# SCH.net
KiCad netlist of a schematic drawn in Altium Designer
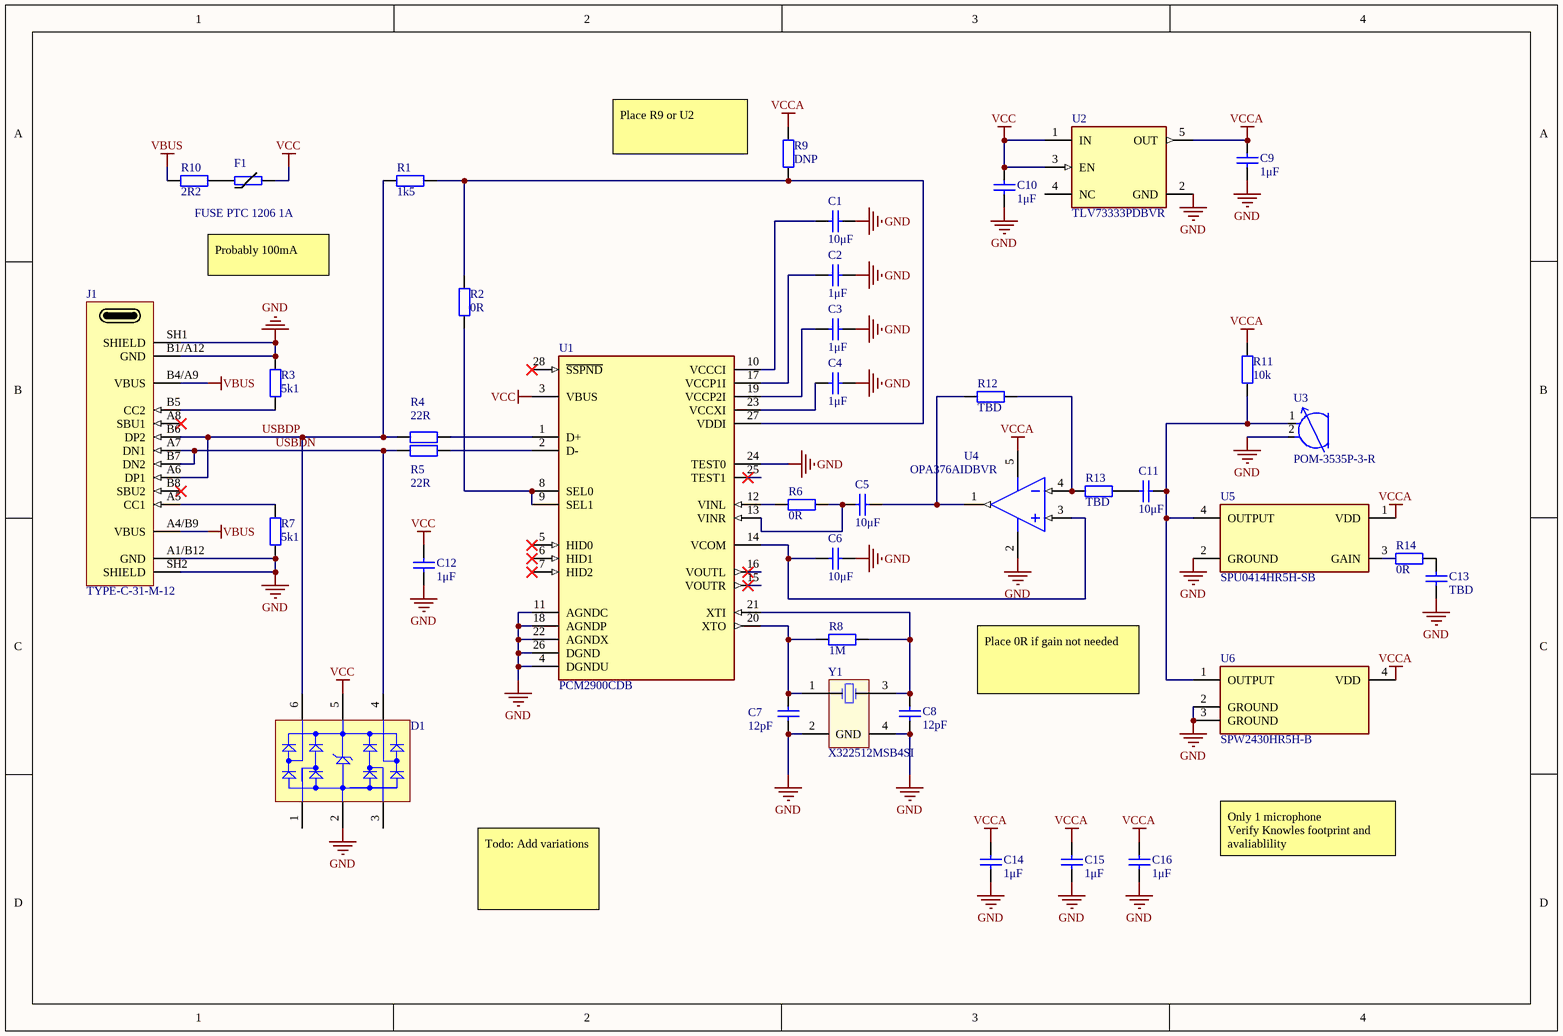
[diagram p0: SCH.SchDoc]

(export (version "E")
  (design (tool "Eeschema 10.0.6"))
  (components
    (comp (ref "C1")
      (value "10μF")
      (footprint "CAPC1206N")
      (description "Multilayer Ceramic Capacitors MLCC - SMD/SMT 10uF 50V 1206 RoHS")
      (fields
        (field (name "MFR") "CL31A106KBHNNNE")
        (field (name "MANUFACTURER") "Samsung Electro-Mechanics")
      )
      (libsource (lib "CAP") (part "Cap"))
    )
    (comp (ref "C2")
      (value "1μF")
      (footprint "CAPC0402N")
      (description "Multilayer Ceramic Capacitors MLCC - SMD/SMT 1uF 25V 0402 RoHS")
      (fields
        (field (name "MFR") "CL05A105KA5NQNC")
        (field (name "MANUFACTURER") "Samsung Electro-Mechanics")
      )
      (libsource (lib "CAP") (part "Cap"))
    )
    (comp (ref "C3")
      (value "1μF")
      (footprint "CAPC0402N")
      (description "Multilayer Ceramic Capacitors MLCC - SMD/SMT 1uF 25V 0402 RoHS")
      (fields
        (field (name "MFR") "CL05A105KA5NQNC")
        (field (name "MANUFACTURER") "Samsung Electro-Mechanics")
      )
      (libsource (lib "CAP") (part "Cap"))
    )
    (comp (ref "C4")
      (value "1μF")
      (footprint "CAPC0402N")
      (description "Multilayer Ceramic Capacitors MLCC - SMD/SMT 1uF 25V 0402 RoHS")
      (fields
        (field (name "MFR") "CL05A105KA5NQNC")
        (field (name "MANUFACTURER") "Samsung Electro-Mechanics")
      )
      (libsource (lib "CAP") (part "Cap"))
    )
    (comp (ref "C5")
      (value "10μF")
      (footprint "CAPC1206N")
      (description "Multilayer Ceramic Capacitors MLCC - SMD/SMT 10uF 50V 1206 RoHS")
      (fields
        (field (name "MFR") "CL31A106KBHNNNE")
        (field (name "MANUFACTURER") "Samsung Electro-Mechanics")
      )
      (libsource (lib "CAP") (part "Cap"))
    )
    (comp (ref "C6")
      (value "10μF")
      (footprint "CAPC1206N")
      (description "Multilayer Ceramic Capacitors MLCC - SMD/SMT 10uF 50V 1206 RoHS")
      (fields
        (field (name "MFR") "CL31A106KBHNNNE")
        (field (name "MANUFACTURER") "Samsung Electro-Mechanics")
      )
      (libsource (lib "CAP") (part "Cap"))
    )
    (comp (ref "C7")
      (value "12pF")
      (footprint "CAPC0402N")
      (description "Multilayer Ceramic Capacitors MLCC - SMD/SMT 12pF 50V 0402 RoHS")
      (fields
        (field (name "MFR") "0402CG120J500NT")
        (field (name "MANUFACTURER") "Guangdong Fenghua Advanced Tech")
      )
      (libsource (lib "CAP") (part "Cap"))
    )
    (comp (ref "C8")
      (value "12pF")
      (footprint "CAPC0402N")
      (description "Multilayer Ceramic Capacitors MLCC - SMD/SMT 12pF 50V 0402 RoHS")
      (fields
        (field (name "MFR") "0402CG120J500NT")
        (field (name "MANUFACTURER") "Guangdong Fenghua Advanced Tech")
      )
      (libsource (lib "CAP") (part "Cap"))
    )
    (comp (ref "C9")
      (value "1μF")
      (footprint "CAPC0402N")
      (description "Multilayer Ceramic Capacitors MLCC - SMD/SMT 1uF 25V 0402 RoHS")
      (fields
        (field (name "MFR") "CL05A105KA5NQNC")
        (field (name "MANUFACTURER") "Samsung Electro-Mechanics")
      )
      (libsource (lib "CAP") (part "Cap"))
    )
    (comp (ref "C10")
      (value "1μF")
      (footprint "CAPC0402N")
      (description "Multilayer Ceramic Capacitors MLCC - SMD/SMT 1uF 25V 0402 RoHS")
      (fields
        (field (name "MFR") "CL05A105KA5NQNC")
        (field (name "MANUFACTURER") "Samsung Electro-Mechanics")
      )
      (libsource (lib "CAP") (part "Cap"))
    )
    (comp (ref "C11")
      (value "10μF")
      (footprint "CAPC1206N")
      (description "Multilayer Ceramic Capacitors MLCC - SMD/SMT 10uF 50V 1206 RoHS")
      (fields
        (field (name "MFR") "CL31A106KBHNNNE")
        (field (name "MANUFACTURER") "Samsung Electro-Mechanics")
      )
      (libsource (lib "CAP") (part "Cap"))
    )
    (comp (ref "C12")
      (value "1μF")
      (footprint "CAPC0402N")
      (description "Multilayer Ceramic Capacitors MLCC - SMD/SMT 1uF 25V 0402 RoHS")
      (fields
        (field (name "MFR") "CL05A105KA5NQNC")
        (field (name "MANUFACTURER") "Samsung Electro-Mechanics")
      )
      (libsource (lib "CAP") (part "Cap"))
    )
    (comp (ref "C13")
      (value "TBD")
      (footprint "CAPC0402N")
      (description "Multilayer Ceramic Capacitors MLCC - SMD/SMT 12pF 50V 0402 RoHS")
      (fields
        (field (name "MFR") "0402CG120J500NT")
        (field (name "MANUFACTURER") "Guangdong Fenghua Advanced Tech")
      )
      (libsource (lib "CAP") (part "Cap"))
    )
    (comp (ref "C14")
      (value "1μF")
      (footprint "CAPC0402N")
      (description "Multilayer Ceramic Capacitors MLCC - SMD/SMT 1uF 25V 0402 RoHS")
      (fields
        (field (name "MFR") "CL05A105KA5NQNC")
        (field (name "MANUFACTURER") "Samsung Electro-Mechanics")
      )
      (libsource (lib "CAP") (part "Cap"))
    )
    (comp (ref "C15")
      (value "1μF")
      (footprint "CAPC0402N")
      (description "Multilayer Ceramic Capacitors MLCC - SMD/SMT 1uF 25V 0402 RoHS")
      (fields
        (field (name "MFR") "CL05A105KA5NQNC")
        (field (name "MANUFACTURER") "Samsung Electro-Mechanics")
      )
      (libsource (lib "CAP") (part "Cap"))
    )
    (comp (ref "C16")
      (value "1μF")
      (footprint "CAPC0402N")
      (description "Multilayer Ceramic Capacitors MLCC - SMD/SMT 1uF 25V 0402 RoHS")
      (fields
        (field (name "MFR") "CL05A105KA5NQNC")
        (field (name "MANUFACTURER") "Samsung Electro-Mechanics")
      )
      (libsource (lib "CAP") (part "Cap"))
    )
    (comp (ref "D1")
      (value "~")
      (footprint "SMTC-SOT23-6_V")
      (fields (field (name "MANUFACTURER") "PROTEK DEVICES") (field (name "MFR") "SRV05-4-P-T7"))
      (libsource (lib "JLC_basic") (part "STM-USB_DVI_HDMIULC6-4SC6X-SOT23-6L"))
    )
    (comp (ref "F1")
      (value "FUSE PTC 1206 1A")
      (footprint "FUSE1206N")
      (fields
        (field (name "VOLTAGE") "6V")
        (field (name "MANUFACTURER") "BOURNS")
        (field (name "MFR") "MF-NSMF050-2")
      )
      (libsource (lib "Fuse") (part "PTC-SMALL"))
    )
    (comp (ref "J1")
      (value "TYPE-C-31-M-12")
      (footprint "TYPE-C-31-M-12")
      (description "USB TYPE-C 2.0 16 PIN SMD")
      (fields (field (name "MANUFACTURER") "Korean Hroparts Elec"))
      (libsource (lib "TYPE-C-31-M-12") (part "TYPE-C-31-M-12"))
    )
    (comp (ref "R1")
      (value "1k5")
      (footprint "RESC0402N")
      (description "Chip Resistor - Surface Mount 1.5KOhms ±1% 1/16W 0402 RoHS")
      (fields (field (name "MFR") "0402WGF1501TCE") (field (name "MANUFACTURER") "Uniroyal Elec"))
      (libsource (lib "RES") (part "Res"))
    )
    (comp (ref "R2")
      (value "0R")
      (footprint "RESC0402N")
      (description "Chip Resistor - Surface Mount 0Ohms ±1% 1/16W 0402 RoHS")
      (fields (field (name "MFR") "0402WGF0000TCE") (field (name "MANUFACTURER") "Uniroyal Elec"))
      (libsource (lib "") (part "Res_1"))
    )
    (comp (ref "R3")
      (value "5k1")
      (footprint "RESC0402N")
      (description "Chip Resistor - Surface Mount 5.1KOhms ±1% 1/16W 0402 RoHS")
      (fields (field (name "MFR") "0402WGF5101TCE") (field (name "MANUFACTURER") "Uniroyal Elec"))
      (libsource (lib "") (part "Res_1"))
    )
    (comp (ref "R4")
      (value "22R")
      (footprint "RESC0402N")
      (description "Chip Resistor - Surface Mount 22Ohms ±1% 1/16W 0402 RoHS")
      (fields (field (name "MFR") "0402WGF220JTCE") (field (name "MANUFACTURER") "Uniroyal Elec"))
      (libsource (lib "RES") (part "Res"))
    )
    (comp (ref "R5")
      (value "22R")
      (footprint "RESC0402N")
      (description "Chip Resistor - Surface Mount 22Ohms ±1% 1/16W 0402 RoHS")
      (fields (field (name "MFR") "0402WGF220JTCE") (field (name "MANUFACTURER") "Uniroyal Elec"))
      (libsource (lib "RES") (part "Res"))
    )
    (comp (ref "R6")
      (value "0R")
      (footprint "RESC0402N")
      (description "Chip Resistor - Surface Mount 0Ohms ±1% 1/16W 0402 RoHS")
      (fields (field (name "MFR") "0402WGF0000TCE") (field (name "MANUFACTURER") "Uniroyal Elec"))
      (libsource (lib "RES") (part "Res"))
    )
    (comp (ref "R7")
      (value "5k1")
      (footprint "RESC0402N")
      (description "Chip Resistor - Surface Mount 5.1KOhms ±1% 1/16W 0402 RoHS")
      (fields (field (name "MFR") "0402WGF5101TCE") (field (name "MANUFACTURER") "Uniroyal Elec"))
      (libsource (lib "") (part "Res_1"))
    )
    (comp (ref "R8")
      (value "1M")
      (footprint "RESC0402N")
      (description "Chip Resistor - Surface Mount 1MOhms ±1% 1/16W 0402 RoHS")
      (fields (field (name "MFR") "0402WGF1004TCE") (field (name "MANUFACTURER") "Uniroyal Elec"))
      (libsource (lib "RES") (part "Res"))
    )
    (comp (ref "R9")
      (value "DNP")
      (footprint "RESC0402N")
      (description "Chip Resistor - Surface Mount 0Ohms ±1% 1/16W 0402 RoHS")
      (fields (field (name "MFR") "0402WGF0000TCE") (field (name "MANUFACTURER") "Uniroyal Elec"))
      (libsource (lib "") (part "Res_1"))
    )
    (comp (ref "R10")
      (value "2R2")
      (footprint "RESC0805N")
      (description "Chip Resistor - Surface Mount 2.2Ohms ±1% 1/8W 0805 RoHS")
      (fields (field (name "MFR") "0805W8F220KT5E") (field (name "MANUFACTURER") "Uniroyal Elec"))
      (libsource (lib "RES") (part "Res"))
    )
    (comp (ref "R11")
      (value "10k")
      (footprint "RESC0402N")
      (description "Chip Resistor - Surface Mount 10KOhms ±1% 1/16W 0402 RoHS")
      (fields (field (name "MFR") "0402WGF1002TCE") (field (name "MANUFACTURER") "Uniroyal Elec"))
      (libsource (lib "") (part "Res_1"))
    )
    (comp (ref "R12")
      (value "TBD")
      (footprint "RESC0402N")
      (description "Chip Resistor - Surface Mount 0Ohms ±1% 1/16W 0402 RoHS")
      (fields (field (name "MFR") "0402WGF0000TCE") (field (name "MANUFACTURER") "Uniroyal Elec"))
      (libsource (lib "RES") (part "Res"))
    )
    (comp (ref "R13")
      (value "TBD")
      (footprint "RESC0402N")
      (description "Chip Resistor - Surface Mount 0Ohms ±1% 1/16W 0402 RoHS")
      (fields (field (name "MFR") "0402WGF0000TCE") (field (name "MANUFACTURER") "Uniroyal Elec"))
      (libsource (lib "RES") (part "Res"))
    )
    (comp (ref "R14")
      (value "0R")
      (footprint "RESC0402N")
      (description "Chip Resistor - Surface Mount 0Ohms ±1% 1/16W 0402 RoHS")
      (fields (field (name "MFR") "0402WGF0000TCE") (field (name "MANUFACTURER") "Uniroyal Elec"))
      (libsource (lib "RES") (part "Res"))
    )
    (comp (ref "U1")
      (value "PCM2900CDB")
      (footprint "FP-DB0028A-IPC_A")
      (description "IC STEREO AUD CODEC W/USB 28SSOP")
      (libsource (lib "Altium Content Vault") (part "18f50380f68bf095b5d7ebbc4dc14fa"))
    )
    (comp (ref "U2")
      (value "TLV73333PDBVR")
      (footprint "FP-DBV0005A-MFG")
      (description "Linear Voltage Regulator IC 1 Output 300mA SOT-23-5")
      (fields (field (name "MANUFACTURER") "Texas Instruments"))
      (libsource (lib "Altium Content Vault") (part "10cdd6a861ce8db355dac0efc8b397e"))
    )
    (comp (ref "U3")
      (value "POM-3535P-3-R")
      (footprint "FP-POM-3535P-3-R-MFG")
      (description "MIC COND ANALOG OMNI -35DB 6MM D")
      (libsource (lib "Altium Content Vault") (part "8932b53fa08aabe3022b5f676529f57"))
    )
    (comp (ref "U4")
      (value "OPA376AIDBVR")
      (footprint "DBV0005A_M")
      (fields (field (name "MANUFACTURER") "Texas Instruments"))
      (libsource (lib "Altium Content Vault") (part "TI-OPA_SM7XXXX-DBV5"))
    )
    (comp (ref "U5")
      (value "SPU0414HR5H-SB")
      (footprint "FP-SPU0414HR5H-SB-MFG")
      (description "MICROPHONE MEMS ANALOG OMNI")
      (libsource (lib "Altium Content Vault") (part "bb2ff92566d391dae9a5852dd65859e"))
    )
    (comp (ref "U6")
      (value "SPW2430HR5H-B")
      (footprint "FP-SPW2430HR5H-B-MFG")
      (description "MICROPHONE MEMS ANALOG OMNI")
      (libsource (lib "Altium Content Vault") (part "11366c5417270ab3945efd6e140c9b8"))
    )
    (comp (ref "Y1")
      (value "X322512MSB4SI")
      (footprint "osccc340x270x100m")
      (description "Crystal Oscillator")
      (fields (field (name "MANUFACTURER") "Yangxing Tech"))
      (libsource (lib "JLC_basic") (part "X322512MSB4SI"))
    )
  )
  (nets
    (net (code "1") (name "/USBDN") (class "Default")
      (node (ref "D1") (pin "4") (pinfunction "I/O_3_4") (pintype "passive"))
      (node (ref "J1") (pin "A7") (pinfunction "DN1_A7") (pintype "input"))
      (node (ref "J1") (pin "B7") (pinfunction "DN2_B7") (pintype "input"))
      (node (ref "R5") (pin "1") (pinfunction "1_1") (pintype "passive"))
    )
    (net (code "2") (name "/USBDP") (class "Default")
      (node (ref "D1") (pin "6") (pinfunction "I/O_4_6") (pintype "passive"))
      (node (ref "J1") (pin "A6") (pinfunction "DP1_A6") (pintype "input"))
      (node (ref "J1") (pin "B6") (pinfunction "DP2_B6") (pintype "input"))
      (node (ref "R1") (pin "1") (pinfunction "1_1") (pintype "passive"))
      (node (ref "R4") (pin "1") (pinfunction "1_1") (pintype "passive"))
    )
    (net (code "3") (name "GND") (class "Default")
      (node (ref "C1") (pin "2") (pinfunction "2_2") (pintype "passive"))
      (node (ref "C10") (pin "1") (pinfunction "1_1") (pintype "passive"))
      (node (ref "C12") (pin "1") (pinfunction "1_1") (pintype "passive"))
      (node (ref "C13") (pin "1") (pinfunction "1_1") (pintype "passive"))
      (node (ref "C14") (pin "1") (pinfunction "1_1") (pintype "passive"))
      (node (ref "C15") (pin "1") (pinfunction "1_1") (pintype "passive"))
      (node (ref "C16") (pin "1") (pinfunction "1_1") (pintype "passive"))
      (node (ref "C2") (pin "2") (pinfunction "2_2") (pintype "passive"))
      (node (ref "C3") (pin "2") (pinfunction "2_2") (pintype "passive"))
      (node (ref "C4") (pin "2") (pinfunction "2_2") (pintype "passive"))
      (node (ref "C6") (pin "2") (pinfunction "2_2") (pintype "passive"))
      (node (ref "C7") (pin "1") (pinfunction "1_1") (pintype "passive"))
      (node (ref "C8") (pin "1") (pinfunction "1_1") (pintype "passive"))
      (node (ref "C9") (pin "1") (pinfunction "1_1") (pintype "passive"))
      (node (ref "D1") (pin "2") (pinfunction "GND_2") (pintype "passive"))
      (node (ref "J1") (pin "A1/B12") (pinfunction "GND_A1/B12") (pintype "power_in"))
      (node (ref "J1") (pin "B1/A12") (pinfunction "GND_B1/A12") (pintype "power_in"))
      (node (ref "J1") (pin "SH1") (pinfunction "SHIELD_SH1") (pintype "power_in"))
      (node (ref "J1") (pin "SH2") (pinfunction "SHIELD_SH2") (pintype "power_in"))
      (node (ref "R3") (pin "2") (pinfunction "2_2") (pintype "passive"))
      (node (ref "R7") (pin "1") (pinfunction "1_1") (pintype "passive"))
      (node (ref "U1") (pin "11") (pinfunction "AGNDC_11") (pintype "power_in"))
      (node (ref "U1") (pin "18") (pinfunction "AGNDP_18") (pintype "power_in"))
      (node (ref "U1") (pin "22") (pinfunction "AGNDX_22") (pintype "power_in"))
      (node (ref "U1") (pin "24") (pinfunction "TEST0_24") (pintype "passive"))
      (node (ref "U1") (pin "26") (pinfunction "DGND_26") (pintype "power_in"))
      (node (ref "U1") (pin "4") (pinfunction "DGNDU_4") (pintype "power_in"))
      (node (ref "U2") (pin "2") (pinfunction "GND_2") (pintype "power_in"))
      (node (ref "U3") (pin "2") (pinfunction "C_2") (pintype "passive"))
      (node (ref "U4") (pin "2") (pinfunction "V-_2") (pintype "power_in"))
      (node (ref "U5") (pin "2") (pinfunction "GROUND_2") (pintype "power_in"))
      (node (ref "U6") (pin "2") (pinfunction "GROUND_2") (pintype "power_in"))
      (node (ref "U6") (pin "3") (pinfunction "GROUND_3") (pintype "power_in"))
      (node (ref "Y1") (pin "2") (pinfunction "2_2") (pintype "passive"))
      (node (ref "Y1") (pin "4") (pinfunction "GND_4") (pintype "power_in"))
    )
    (net (code "4") (name "Net-(C11-Pad1)") (class "Default")
      (node (ref "C11") (pin "1") (pinfunction "1_1") (pintype "passive"))
      (node (ref "R13") (pin "2") (pinfunction "2_2") (pintype "passive"))
    )
    (net (code "5") (name "Net-(C13-Pad2)") (class "Default")
      (node (ref "C13") (pin "2") (pinfunction "2_2") (pintype "passive"))
      (node (ref "R14") (pin "2") (pinfunction "2_2") (pintype "passive"))
    )
    (net (code "6") (name "Net-(F1-Pad1)") (class "Default")
      (node (ref "F1") (pin "1") (pinfunction "1_1") (pintype "passive"))
      (node (ref "R10") (pin "2") (pinfunction "2_2") (pintype "passive"))
    )
    (net (code "7") (name "Net-(J1-CC1)") (class "Default")
      (node (ref "J1") (pin "A5") (pinfunction "CC1_A5") (pintype "input"))
      (node (ref "R7") (pin "2") (pinfunction "2_2") (pintype "passive"))
    )
    (net (code "8") (name "Net-(J1-CC2)") (class "Default")
      (node (ref "J1") (pin "B5") (pinfunction "CC2_B5") (pintype "input"))
      (node (ref "R3") (pin "1") (pinfunction "1_1") (pintype "passive"))
    )
    (net (code "9") (name "Net-(U1-D+)") (class "Default")
      (node (ref "R4") (pin "2") (pinfunction "2_2") (pintype "passive"))
      (node (ref "U1") (pin "1") (pinfunction "D+_1") (pintype "tri_state"))
    )
    (net (code "10") (name "Net-(U1-D-)") (class "Default")
      (node (ref "R5") (pin "2") (pinfunction "2_2") (pintype "passive"))
      (node (ref "U1") (pin "2") (pinfunction "D-_2") (pintype "tri_state"))
    )
    (net (code "11") (name "Net-(U1-SEL0)") (class "Default")
      (node (ref "R2") (pin "1") (pinfunction "1_1") (pintype "passive"))
      (node (ref "U1") (pin "8") (pinfunction "SEL0_8") (pintype "open_collector"))
      (node (ref "U1") (pin "9") (pinfunction "SEL1_9") (pintype "open_collector"))
    )
    (net (code "12") (name "Net-(U1-VCCCI)") (class "Default")
      (node (ref "C1") (pin "1") (pinfunction "1_1") (pintype "passive"))
      (node (ref "U1") (pin "10") (pinfunction "VCCCI_10") (pintype "power_in"))
    )
    (net (code "13") (name "Net-(U1-VCCP1I)") (class "Default")
      (node (ref "C2") (pin "1") (pinfunction "1_1") (pintype "passive"))
      (node (ref "U1") (pin "17") (pinfunction "VCCP1I_17") (pintype "power_in"))
    )
    (net (code "14") (name "Net-(U1-VCCP2I)") (class "Default")
      (node (ref "C3") (pin "1") (pinfunction "1_1") (pintype "passive"))
      (node (ref "U1") (pin "19") (pinfunction "VCCP2I_19") (pintype "power_in"))
    )
    (net (code "15") (name "Net-(U1-VCCXI)") (class "Default")
      (node (ref "C4") (pin "1") (pinfunction "1_1") (pintype "passive"))
      (node (ref "U1") (pin "23") (pinfunction "VCCXI_23") (pintype "power_in"))
    )
    (net (code "16") (name "Net-(U1-VCOM)") (class "Default")
      (node (ref "C6") (pin "1") (pinfunction "1_1") (pintype "passive"))
      (node (ref "U1") (pin "14") (pinfunction "VCOM_14") (pintype "passive"))
      (node (ref "U4") (pin "3") (pinfunction "IN+_3") (pintype "input"))
    )
    (net (code "17") (name "Net-(U1-VDDI)") (class "Default")
      (node (ref "R1") (pin "2") (pinfunction "2_2") (pintype "passive"))
      (node (ref "R2") (pin "2") (pinfunction "2_2") (pintype "passive"))
      (node (ref "R9") (pin "1") (pinfunction "1_1") (pintype "passive"))
      (node (ref "U1") (pin "27") (pinfunction "VDDI_27") (pintype "power_in"))
    )
    (net (code "18") (name "Net-(U1-VINL)") (class "Default")
      (node (ref "R6") (pin "1") (pinfunction "1_1") (pintype "passive"))
      (node (ref "U1") (pin "12") (pinfunction "VINL_12") (pintype "input"))
    )
    (net (code "19") (name "Net-(U1-VINR)") (class "Default")
      (node (ref "C5") (pin "1") (pinfunction "1_1") (pintype "passive"))
      (node (ref "R6") (pin "2") (pinfunction "2_2") (pintype "passive"))
      (node (ref "U1") (pin "13") (pinfunction "VINR_13") (pintype "input"))
    )
    (net (code "20") (name "Net-(U1-XTI)") (class "Default")
      (node (ref "C8") (pin "2") (pinfunction "2_2") (pintype "passive"))
      (node (ref "R8") (pin "2") (pinfunction "2_2") (pintype "passive"))
      (node (ref "U1") (pin "21") (pinfunction "XTI_21") (pintype "input"))
      (node (ref "Y1") (pin "3") (pinfunction "OSC2_3") (pintype "passive"))
    )
    (net (code "21") (name "Net-(U1-XTO)") (class "Default")
      (node (ref "C7") (pin "2") (pinfunction "2_2") (pintype "passive"))
      (node (ref "R8") (pin "1") (pinfunction "1_1") (pintype "passive"))
      (node (ref "U1") (pin "20") (pinfunction "XTO_20") (pintype "output"))
      (node (ref "Y1") (pin "1") (pinfunction "OSC1_1") (pintype "passive"))
    )
    (net (code "22") (name "Net-(U3-A)") (class "Default")
      (node (ref "C11") (pin "2") (pinfunction "2_2") (pintype "passive"))
      (node (ref "R11") (pin "1") (pinfunction "1_1") (pintype "passive"))
      (node (ref "U3") (pin "1") (pinfunction "A_1") (pintype "passive"))
      (node (ref "U5") (pin "4") (pinfunction "OUTPUT_4") (pintype "passive"))
      (node (ref "U6") (pin "1") (pinfunction "OUTPUT_1") (pintype "passive"))
    )
    (net (code "23") (name "Net-(U4-IN-)") (class "Default")
      (node (ref "R12") (pin "2") (pinfunction "2_2") (pintype "passive"))
      (node (ref "R13") (pin "1") (pinfunction "1_1") (pintype "passive"))
      (node (ref "U4") (pin "4") (pinfunction "IN-_4") (pintype "input"))
    )
    (net (code "24") (name "Net-(U4-OUT)") (class "Default")
      (node (ref "C5") (pin "2") (pinfunction "2_2") (pintype "passive"))
      (node (ref "R12") (pin "1") (pinfunction "1_1") (pintype "passive"))
      (node (ref "U4") (pin "1") (pinfunction "OUT_1") (pintype "output"))
    )
    (net (code "25") (name "Net-(U5-GAIN)") (class "Default")
      (node (ref "R14") (pin "1") (pinfunction "1_1") (pintype "passive"))
      (node (ref "U5") (pin "3") (pinfunction "GAIN_3") (pintype "passive"))
    )
    (net (code "26") (name "VBUS") (class "Default")
      (node (ref "J1") (pin "A4/B9") (pinfunction "VBUS_A4/B9") (pintype "power_in"))
      (node (ref "J1") (pin "B4/A9") (pinfunction "VBUS_B4/A9") (pintype "power_in"))
      (node (ref "R10") (pin "1") (pinfunction "1_1") (pintype "passive"))
    )
    (net (code "27") (name "VCC") (class "Default")
      (node (ref "C10") (pin "2") (pinfunction "2_2") (pintype "passive"))
      (node (ref "C12") (pin "2") (pinfunction "2_2") (pintype "passive"))
      (node (ref "D1") (pin "5") (pinfunction "VBUS_5") (pintype "passive"))
      (node (ref "F1") (pin "2") (pinfunction "2_2") (pintype "passive"))
      (node (ref "U1") (pin "3") (pinfunction "VBUS_3") (pintype "power_in"))
      (node (ref "U2") (pin "1") (pinfunction "IN_1") (pintype "power_in"))
      (node (ref "U2") (pin "3") (pinfunction "EN_3") (pintype "input"))
    )
    (net (code "28") (name "VCCA") (class "Default")
      (node (ref "C14") (pin "2") (pinfunction "2_2") (pintype "passive"))
      (node (ref "C15") (pin "2") (pinfunction "2_2") (pintype "passive"))
      (node (ref "C16") (pin "2") (pinfunction "2_2") (pintype "passive"))
      (node (ref "C9") (pin "2") (pinfunction "2_2") (pintype "passive"))
      (node (ref "R11") (pin "2") (pinfunction "2_2") (pintype "passive"))
      (node (ref "R9") (pin "2") (pinfunction "2_2") (pintype "passive"))
      (node (ref "U2") (pin "5") (pinfunction "OUT_5") (pintype "output"))
      (node (ref "U4") (pin "5") (pinfunction "V+_5") (pintype "power_in"))
      (node (ref "U5") (pin "1") (pinfunction "VDD_1") (pintype "power_in"))
      (node (ref "U6") (pin "4") (pinfunction "VDD_4") (pintype "power_in"))
    )
    (net (code "29") (name "unconnected-(D1-I{slash}O_1-Pad1)") (class "Default")
      (node (ref "D1") (pin "1") (pinfunction "I/O_1_1") (pintype "passive"))
    )
    (net (code "30") (name "unconnected-(D1-I{slash}O_2-Pad3)") (class "Default")
      (node (ref "D1") (pin "3") (pinfunction "I/O_2_3") (pintype "passive"))
    )
    (net (code "31") (name "unconnected-(J1-SBU1-PadA8)") (class "Default")
      (node (ref "J1") (pin "A8") (pinfunction "SBU1_A8") (pintype "input+no_connect"))
    )
    (net (code "32") (name "unconnected-(J1-SBU2-PadB8)") (class "Default")
      (node (ref "J1") (pin "B8") (pinfunction "SBU2_B8") (pintype "input+no_connect"))
    )
    (net (code "33") (name "unconnected-(U1-HID0-Pad5)") (class "Default")
      (node (ref "U1") (pin "5") (pinfunction "HID0_5") (pintype "input+no_connect"))
    )
    (net (code "34") (name "unconnected-(U1-HID1-Pad6)") (class "Default")
      (node (ref "U1") (pin "6") (pinfunction "HID1_6") (pintype "input+no_connect"))
    )
    (net (code "35") (name "unconnected-(U1-HID2-Pad7)") (class "Default")
      (node (ref "U1") (pin "7") (pinfunction "HID2_7") (pintype "input+no_connect"))
    )
    (net (code "36") (name "unconnected-(U1-TEST1-Pad25)") (class "Default")
      (node (ref "U1") (pin "25") (pinfunction "TEST1_25") (pintype "passive+no_connect"))
    )
    (net (code "37") (name "unconnected-(U1-VOUTL-Pad16)") (class "Default")
      (node (ref "U1") (pin "16") (pinfunction "VOUTL_16") (pintype "output+no_connect"))
    )
    (net (code "38") (name "unconnected-(U1-VOUTR-Pad15)") (class "Default")
      (node (ref "U1") (pin "15") (pinfunction "VOUTR_15") (pintype "output+no_connect"))
    )
    (net (code "39") (name "unconnected-(U1-~{SSPND}-Pad28)") (class "Default")
      (node (ref "U1") (pin "28") (pinfunction "~{SSPND}_28") (pintype "input+no_connect"))
    )
    (net (code "40") (name "unconnected-(U2-NC-Pad4)") (class "Default")
      (node (ref "U2") (pin "4") (pinfunction "NC_4") (pintype "passive"))
    )
  )
)
